# ESP32_USBC.net
KiCad netlist of a schematic drawn in Altium Designer
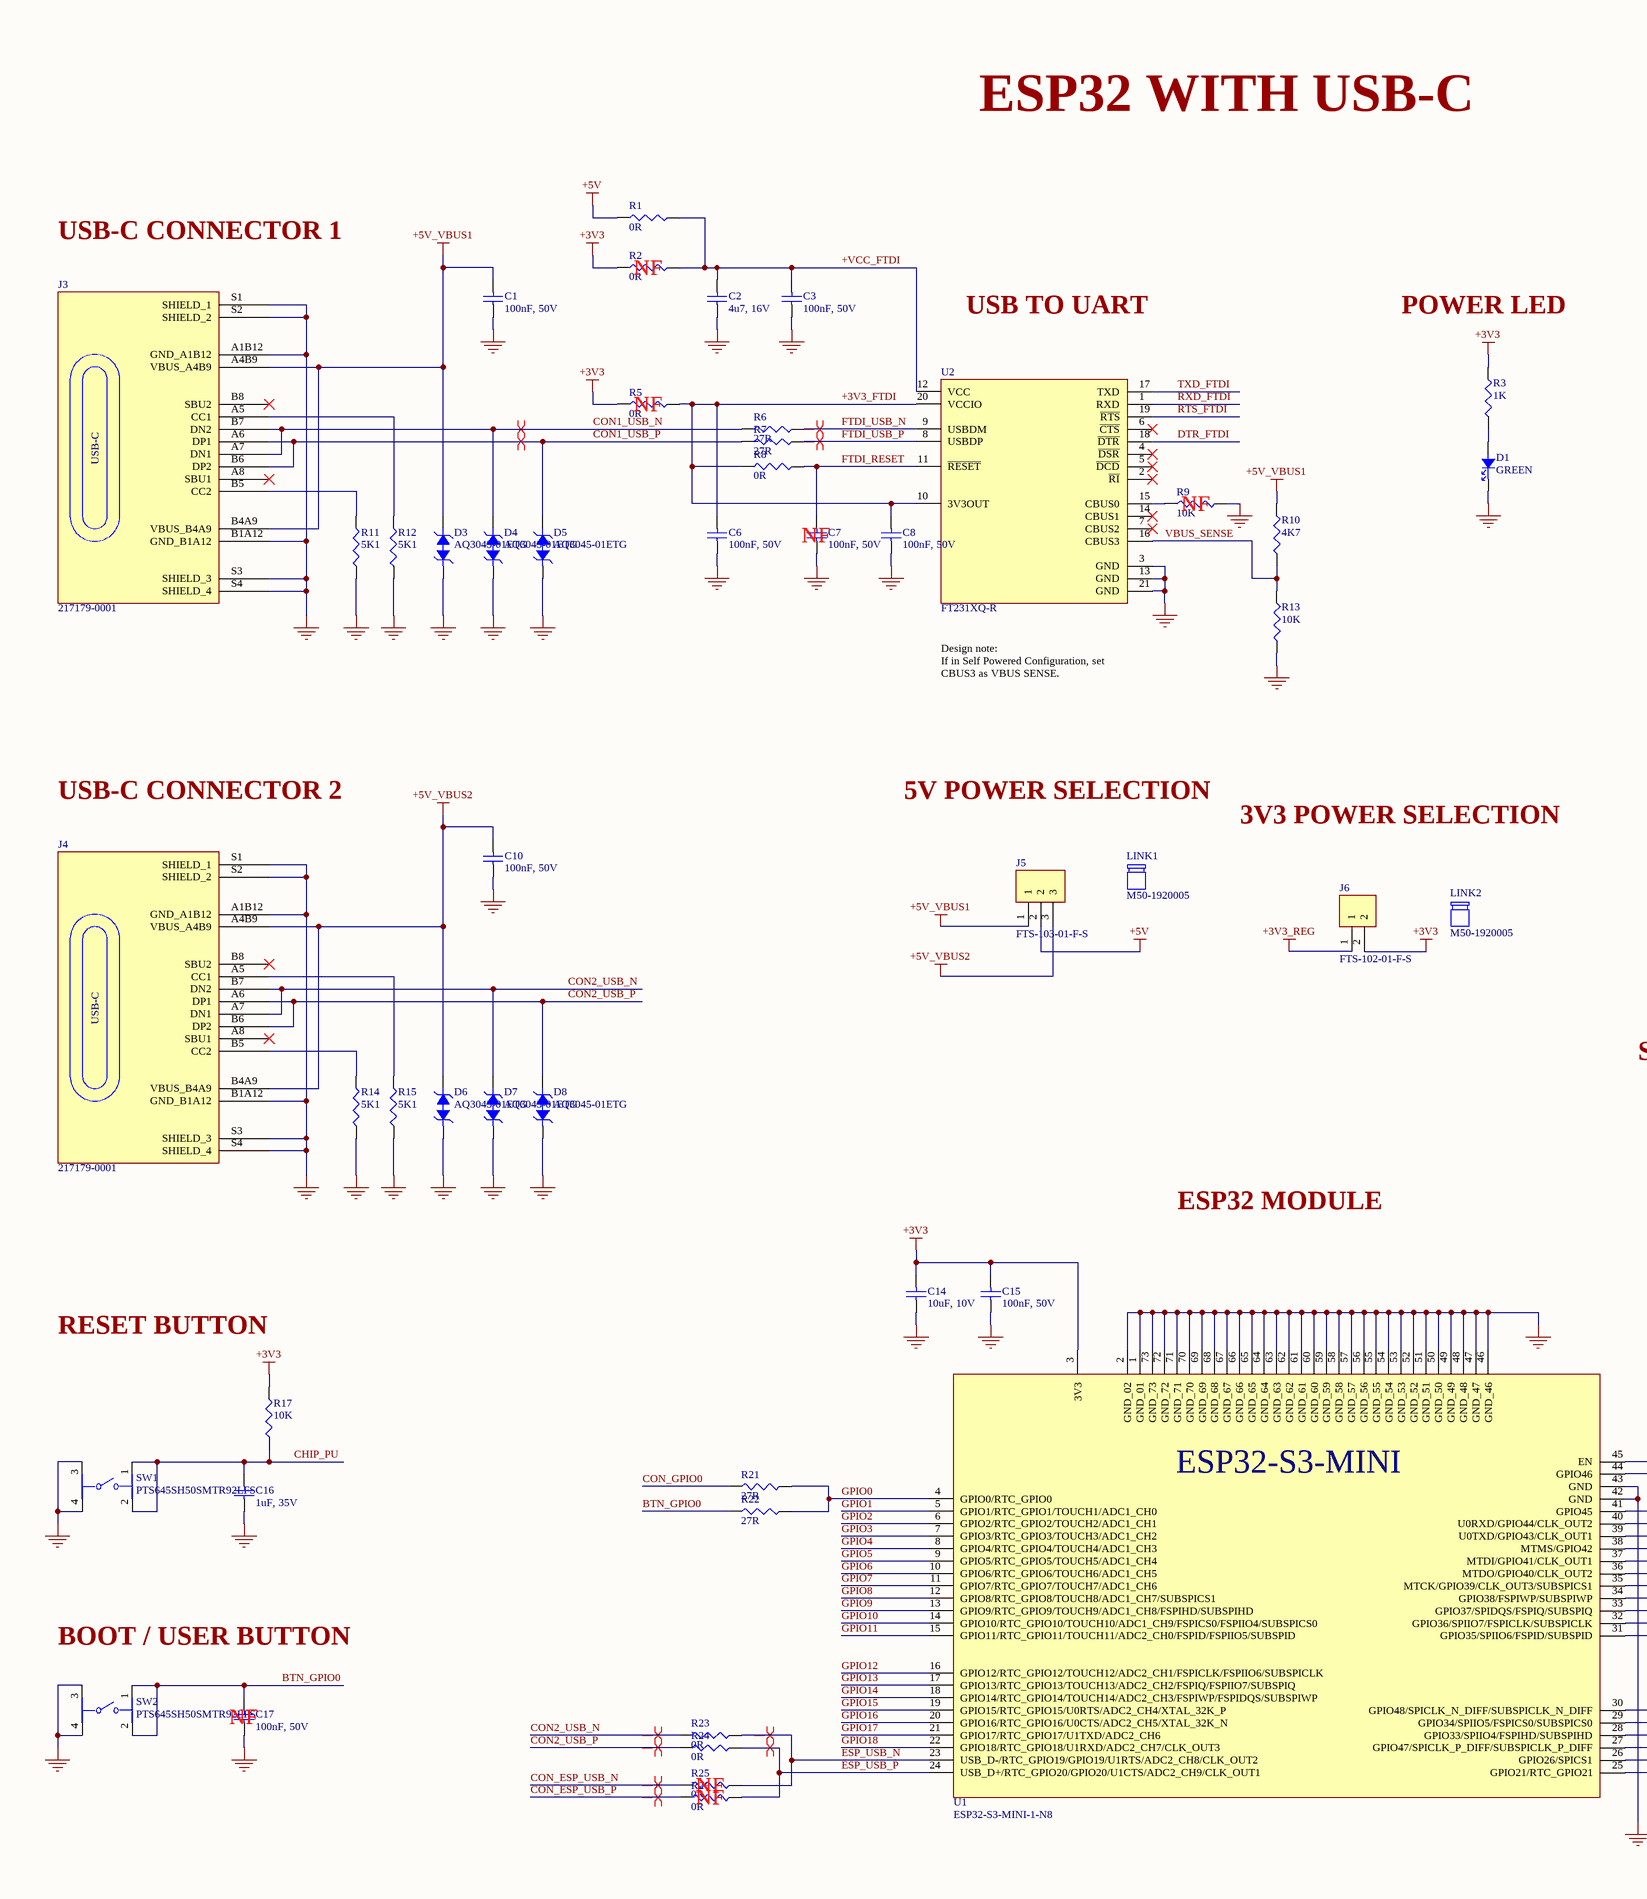
[diagram p0: ESP32_USBC.SchDoc, left]
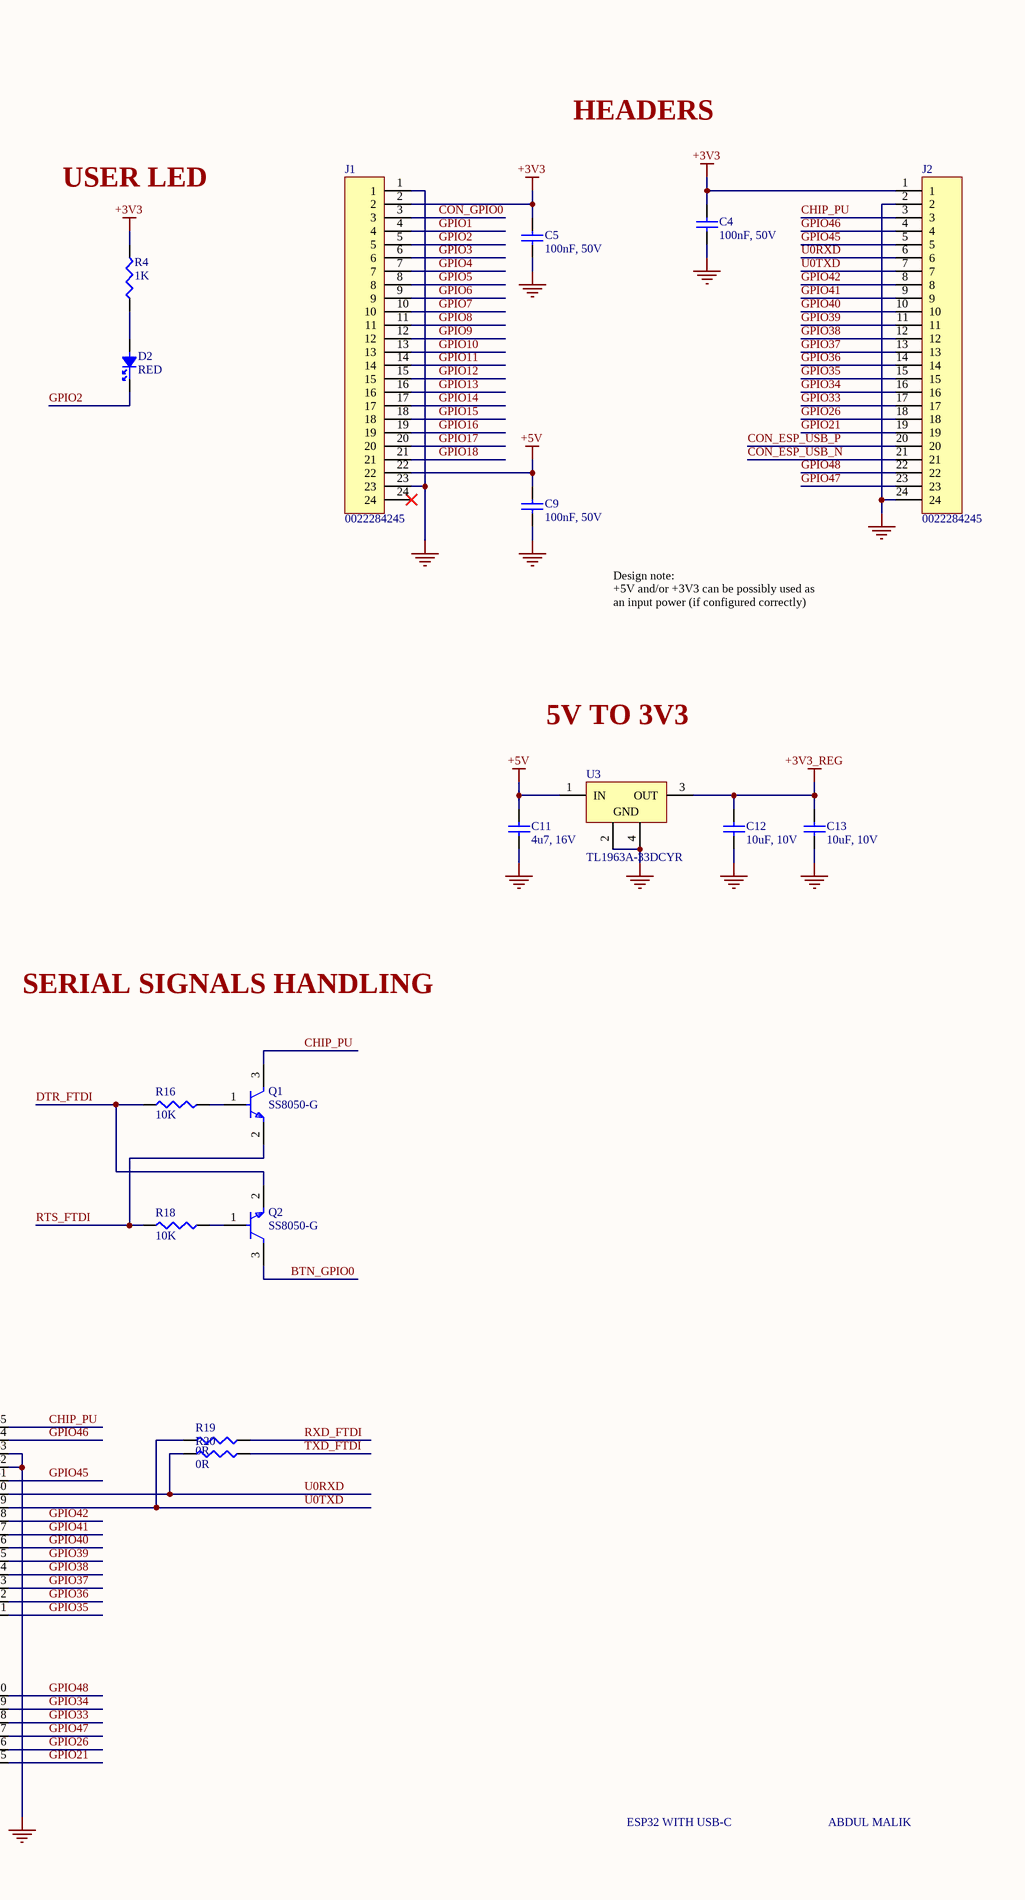
[diagram p1: ESP32_USBC.SchDoc, right]

(export (version "E")
  (design (tool "Eeschema 10.0.6"))
  (components
    (comp (ref "C1")
      (value "100nF, 50V")
      (footprint "CAPC1005X55N")
      (description "CAP CER 0.1UF 50V X7R 0402")
      (fields
        (field (name "MANUFACTURER") "Samsung")
        (field (name "MANUFACTURER PART NUMBER") "CL05B104KB54PNC")
      )
      (libsource (lib "Schlib") (part "CL05B104KB54PNC"))
    )
    (comp (ref "C2")
      (value "4u7, 16V")
      (footprint "CAPC1005X55N")
      (description "CAP CER 4.7UF 16V X5R 0402")
      (fields
        (field (name "MANUFACTURER") "Samsung")
        (field (name "MANUFACTURER PART NUMBER") "CL05A475MO5NUNC")
      )
      (libsource (lib "Schlib") (part "CL05A475MO5NUNC"))
    )
    (comp (ref "C3")
      (value "100nF, 50V")
      (footprint "CAPC1005X55N")
      (description "CAP CER 0.1UF 50V X7R 0402")
      (fields
        (field (name "MANUFACTURER") "Samsung")
        (field (name "MANUFACTURER PART NUMBER") "CL05B104KB54PNC")
      )
      (libsource (lib "Schlib") (part "CL05B104KB54PNC"))
    )
    (comp (ref "C4")
      (value "100nF, 50V")
      (footprint "CAPC1005X55N")
      (description "CAP CER 0.1UF 50V X7R 0402")
      (fields
        (field (name "MANUFACTURER") "Samsung")
        (field (name "MANUFACTURER PART NUMBER") "CL05B104KB54PNC")
      )
      (libsource (lib "Schlib") (part "CL05B104KB54PNC"))
    )
    (comp (ref "C5")
      (value "100nF, 50V")
      (footprint "CAPC1005X55N")
      (description "CAP CER 0.1UF 50V X7R 0402")
      (fields
        (field (name "MANUFACTURER") "Samsung")
        (field (name "MANUFACTURER PART NUMBER") "CL05B104KB54PNC")
      )
      (libsource (lib "Schlib") (part "CL05B104KB54PNC"))
    )
    (comp (ref "C6")
      (value "100nF, 50V")
      (footprint "CAPC1005X55N")
      (description "CAP CER 0.1UF 50V X7R 0402")
      (fields
        (field (name "MANUFACTURER") "Samsung")
        (field (name "MANUFACTURER PART NUMBER") "CL05B104KB54PNC")
      )
      (libsource (lib "Schlib") (part "CL05B104KB54PNC"))
    )
    (comp (ref "C7")
      (value "100nF, 50V")
      (footprint "CAPC1005X55N")
      (description "CAP CER 0.1UF 50V X7R 0402")
      (fields
        (field (name "MANUFACTURER") "Samsung")
        (field (name "MANUFACTURER PART NUMBER") "CL05B104KB54PNC")
      )
      (libsource (lib "Schlib") (part "CL05B104KB54PNC"))
    )
    (comp (ref "C8")
      (value "100nF, 50V")
      (footprint "CAPC1005X55N")
      (description "CAP CER 0.1UF 50V X7R 0402")
      (fields
        (field (name "MANUFACTURER") "Samsung")
        (field (name "MANUFACTURER PART NUMBER") "CL05B104KB54PNC")
      )
      (libsource (lib "Schlib") (part "CL05B104KB54PNC"))
    )
    (comp (ref "C9")
      (value "100nF, 50V")
      (footprint "CAPC1005X55N")
      (description "CAP CER 0.1UF 50V X7R 0402")
      (fields
        (field (name "MANUFACTURER") "Samsung")
        (field (name "MANUFACTURER PART NUMBER") "CL05B104KB54PNC")
      )
      (libsource (lib "Schlib") (part "CL05B104KB54PNC"))
    )
    (comp (ref "C10")
      (value "100nF, 50V")
      (footprint "CAPC1005X55N")
      (description "CAP CER 0.1UF 50V X7R 0402")
      (fields
        (field (name "MANUFACTURER") "Samsung")
        (field (name "MANUFACTURER PART NUMBER") "CL05B104KB54PNC")
      )
      (libsource (lib "Schlib") (part "CL05B104KB54PNC"))
    )
    (comp (ref "C11")
      (value "4u7, 16V")
      (footprint "CAPC1005X55N")
      (description "CAP CER 4.7UF 16V X5R 0402")
      (fields
        (field (name "MANUFACTURER") "Samsung")
        (field (name "MANUFACTURER PART NUMBER") "CL05A475MO5NUNC")
      )
      (libsource (lib "Schlib") (part "CL05A475MO5NUNC"))
    )
    (comp (ref "C12")
      (value "10uF, 10V")
      (footprint "CAPC1005X55N")
      (description "CAP CER 10UF 10V X5R 0402")
      (fields
        (field (name "MANUFACTURER") "Samsung")
        (field (name "MANUFACTURER PART NUMBER") "CL05A106MP8NUB8")
      )
      (libsource (lib "Schlib") (part "CL05A106MP8NUB8"))
    )
    (comp (ref "C13")
      (value "10uF, 10V")
      (footprint "CAPC1005X55N")
      (description "CAP CER 10UF 10V X5R 0402")
      (fields
        (field (name "MANUFACTURER") "Samsung")
        (field (name "MANUFACTURER PART NUMBER") "CL05A106MP8NUB8")
      )
      (libsource (lib "Schlib") (part "CL05A106MP8NUB8"))
    )
    (comp (ref "C14")
      (value "10uF, 10V")
      (footprint "CAPC1005X55N")
      (description "CAP CER 10UF 10V X5R 0402")
      (fields
        (field (name "MANUFACTURER") "Samsung")
        (field (name "MANUFACTURER PART NUMBER") "CL05A106MP8NUB8")
      )
      (libsource (lib "Schlib") (part "CL05A106MP8NUB8"))
    )
    (comp (ref "C15")
      (value "100nF, 50V")
      (footprint "CAPC1005X55N")
      (description "CAP CER 0.1UF 50V X7R 0402")
      (fields
        (field (name "MANUFACTURER") "Samsung")
        (field (name "MANUFACTURER PART NUMBER") "CL05B104KB54PNC")
      )
      (libsource (lib "Schlib") (part "CL05B104KB54PNC"))
    )
    (comp (ref "C16")
      (value "1uF, 35V")
      (footprint "CAPC1005X55N")
      (description "CAP CER 1UF 35V X5R 0402")
      (fields
        (field (name "MANUFACTURER") "Samsung")
        (field (name "MANUFACTURER PART NUMBER") "CL05A105KL5NRNC")
      )
      (libsource (lib "Schlib") (part "CL05A105KL5NRNC"))
    )
    (comp (ref "C17")
      (value "100nF, 50V")
      (footprint "CAPC1005X55N")
      (description "CAP CER 0.1UF 50V X7R 0402")
      (fields
        (field (name "MANUFACTURER") "Samsung")
        (field (name "MANUFACTURER PART NUMBER") "CL05B104KB54PNC")
      )
      (libsource (lib "Schlib") (part "CL05B104KB54PNC"))
    )
    (comp (ref "D1")
      (value "GREEN")
      (footprint "LED0402G")
      (description "LED YLW-GRN 0402 SMD")
      (fields
        (field (name "MANUFACTURER") "Vishay")
        (field (name "MANUFACTURER PART NUMBER") "VLMG1500-GS08")
      )
      (libsource (lib "Schlib") (part "VLMG1500-GS08"))
    )
    (comp (ref "D2")
      (value "RED")
      (footprint "LED0402R")
      (description "LED RED 0402 SMD")
      (fields
        (field (name "MANUFACTURER") "Vishay")
        (field (name "MANUFACTURER PART NUMBER") "VLMS1500-GS08")
      )
      (libsource (lib "Schlib") (part "VLMS1500-GS08"))
    )
    (comp (ref "D3")
      (value "AQ3045-01ETG")
      (footprint "SOD882")
      (description "TVS DIODE 5.3VWM 12VC SOD882")
      (fields (field (name "MANUFACTURER") "Littelfuse") (field (name "LCSC PART NUMBER") "C3710326"))
      (libsource (lib "Schlib") (part "AQ3045-01ETG"))
    )
    (comp (ref "D4")
      (value "AQ3045-01ETG")
      (footprint "SOD882")
      (description "TVS DIODE 5.3VWM 12VC SOD882")
      (fields (field (name "MANUFACTURER") "Littelfuse") (field (name "LCSC PART NUMBER") "C3710326"))
      (libsource (lib "Schlib") (part "AQ3045-01ETG"))
    )
    (comp (ref "D5")
      (value "AQ3045-01ETG")
      (footprint "SOD882")
      (description "TVS DIODE 5.3VWM 12VC SOD882")
      (fields (field (name "MANUFACTURER") "Littelfuse") (field (name "LCSC PART NUMBER") "C3710326"))
      (libsource (lib "Schlib") (part "AQ3045-01ETG"))
    )
    (comp (ref "D6")
      (value "AQ3045-01ETG")
      (footprint "SOD882")
      (description "TVS DIODE 5.3VWM 12VC SOD882")
      (fields (field (name "MANUFACTURER") "Littelfuse") (field (name "LCSC PART NUMBER") "C3710326"))
      (libsource (lib "Schlib") (part "AQ3045-01ETG"))
    )
    (comp (ref "D7")
      (value "AQ3045-01ETG")
      (footprint "SOD882")
      (description "TVS DIODE 5.3VWM 12VC SOD882")
      (fields (field (name "MANUFACTURER") "Littelfuse") (field (name "LCSC PART NUMBER") "C3710326"))
      (libsource (lib "Schlib") (part "AQ3045-01ETG"))
    )
    (comp (ref "D8")
      (value "AQ3045-01ETG")
      (footprint "SOD882")
      (description "TVS DIODE 5.3VWM 12VC SOD882")
      (fields (field (name "MANUFACTURER") "Littelfuse") (field (name "LCSC PART NUMBER") "C3710326"))
      (libsource (lib "Schlib") (part "AQ3045-01ETG"))
    )
    (comp (ref "J1")
      (value "0022284245")
      (footprint "HDR_1X24_2.54MM")
      (description "CONN HEADER VERT 24POS 2.54MM")
      (fields (field (name "MANUFACTURER") "Molex") (field (name "LCSC PART NUMBER") "C7145888"))
      (libsource (lib "") (part "0022284245_1"))
    )
    (comp (ref "J2")
      (value "0022284245")
      (footprint "HDR_1X24_2.54MM")
      (description "CONN HEADER VERT 24POS 2.54MM")
      (fields (field (name "MANUFACTURER") "Molex") (field (name "LCSC PART NUMBER") "C7145888"))
      (libsource (lib "Schlib") (part "0022284245"))
    )
    (comp (ref "J3")
      (value "217179-0001")
      (footprint "FP-2171790001-MFG")
      (description "CONN RCP USB2.0 TYP C 24P SMD RA")
      (fields (field (name "MANUFACTURER") "Molex") (field (name "LCSC PART NUMBER") "C3197684"))
      (libsource (lib "Schlib") (part "217179-0001"))
    )
    (comp (ref "J4")
      (value "217179-0001")
      (footprint "FP-2171790001-MFG")
      (description "CONN RCP USB2.0 TYP C 24P SMD RA")
      (fields (field (name "MANUFACTURER") "Molex") (field (name "LCSC PART NUMBER") "C3197684"))
      (libsource (lib "Schlib") (part "217179-0001"))
    )
    (comp (ref "J5")
      (value "FTS-103-01-F-S")
      (footprint "HDR_1X3_1.27MM")
      (description "CONN HEADER VERT 3POS 1.27MM")
      (fields (field (name "MANUFACTURER") "Samtec") (field (name "LCSC PART NUMBER") "C3333578"))
      (libsource (lib "Schlib") (part "FTS-103-01-F-S"))
    )
    (comp (ref "J6")
      (value "FTS-102-01-F-S")
      (footprint "HDR_1X2_1.27MM")
      (description "CONN HEADER VERT 2POS 1.27MM")
      (fields (field (name "MANUFACTURER") "Samtec") (field (name "LCSC PART NUMBER") "C6045317"))
      (libsource (lib "Schlib") (part "FTS-102-01-F-S"))
    )
    (comp (ref "LINK1")
      (value "M50-1920005")
      (description "CONN SHUNT 1.27MM RED")
      (fields (field (name "MANUFACTURER") "Harwin") (field (name "LCSC PART NUMBER") "C6985646"))
      (libsource (lib "Schlib") (part "M50-1920005"))
    )
    (comp (ref "LINK2")
      (value "M50-1920005")
      (description "CONN SHUNT 1.27MM RED")
      (fields (field (name "MANUFACTURER") "Harwin") (field (name "LCSC PART NUMBER") "C6985646"))
      (libsource (lib "Schlib") (part "M50-1920005"))
    )
    (comp (ref "Q1")
      (value "SS8050-G")
      (footprint "FP-SS8050-G-IPC_B")
      (description "TRANS NPN 25V 1.5A SOT23-3")
      (fields (field (name "MANUFACTURER") "Comchip") (field (name "LCSC PART NUMBER") "C164886"))
      (libsource (lib "Schlib") (part "SS8050-G"))
    )
    (comp (ref "Q2")
      (value "SS8050-G")
      (footprint "FP-SS8050-G-IPC_B")
      (description "TRANS NPN 25V 1.5A SOT23-3")
      (fields (field (name "MANUFACTURER") "Comchip") (field (name "LCSC PART NUMBER") "C164886"))
      (libsource (lib "Schlib") (part "SS8050-G"))
    )
    (comp (ref "R1")
      (value "0R")
      (footprint "RESC1005X37N")
      (description "RES 0 OHM JUMPER 1/16W 0402")
      (fields
        (field (name "MANUFACTURER") "Yageo")
        (field (name "MANUFACTURER PART NUMBER") "RC0402JR-070RL")
      )
      (libsource (lib "Schlib") (part "RC0402JR-070RL"))
    )
    (comp (ref "R2")
      (value "0R")
      (footprint "RESC1005X37N")
      (description "RES 0 OHM JUMPER 1/16W 0402")
      (fields
        (field (name "MANUFACTURER") "Yageo")
        (field (name "MANUFACTURER PART NUMBER") "RC0402JR-070RL")
      )
      (libsource (lib "Schlib") (part "RC0402JR-070RL"))
    )
    (comp (ref "R3")
      (value "1K")
      (footprint "RESC1005X37N")
      (description "RES 1K OHM 1% 1/16W 0402")
      (fields
        (field (name "MANUFACTURER") "Yageo")
        (field (name "MANUFACTURER PART NUMBER") "RC0402FR-071KL")
      )
      (libsource (lib "Schlib") (part "RC0402FR-071KL"))
    )
    (comp (ref "R4")
      (value "1K")
      (footprint "RESC1005X37N")
      (description "RES 1K OHM 1% 1/16W 0402")
      (fields
        (field (name "MANUFACTURER") "Yageo")
        (field (name "MANUFACTURER PART NUMBER") "RC0402FR-071KL")
      )
      (libsource (lib "Schlib") (part "RC0402FR-071KL"))
    )
    (comp (ref "R5")
      (value "0R")
      (footprint "RESC1005X37N")
      (description "RES 0 OHM JUMPER 1/16W 0402")
      (fields
        (field (name "MANUFACTURER") "Yageo")
        (field (name "MANUFACTURER PART NUMBER") "RC0402JR-070RL")
      )
      (libsource (lib "Schlib") (part "RC0402JR-070RL"))
    )
    (comp (ref "R6")
      (value "27R")
      (footprint "RESC1005X37N")
      (description "RES 27 OHM 1% 1/16W 0402")
      (fields
        (field (name "MANUFACTURER") "Yageo")
        (field (name "MANUFACTURER PART NUMBER") "RC0402FR-0727RL")
      )
      (libsource (lib "Schlib") (part "RC0402FR-0727RL"))
    )
    (comp (ref "R7")
      (value "27R")
      (footprint "RESC1005X37N")
      (description "RES 27 OHM 1% 1/16W 0402")
      (fields
        (field (name "MANUFACTURER") "Yageo")
        (field (name "MANUFACTURER PART NUMBER") "RC0402FR-0727RL")
      )
      (libsource (lib "Schlib") (part "RC0402FR-0727RL"))
    )
    (comp (ref "R8")
      (value "0R")
      (footprint "RESC1005X37N")
      (description "RES 0 OHM JUMPER 1/16W 0402")
      (fields
        (field (name "MANUFACTURER") "Yageo")
        (field (name "MANUFACTURER PART NUMBER") "RC0402JR-070RL")
      )
      (libsource (lib "Schlib") (part "RC0402JR-070RL"))
    )
    (comp (ref "R9")
      (value "10K")
      (footprint "RESC1005X37N")
      (description "RES SMD 10K OHM 1% 1/16W 0402")
      (fields
        (field (name "MANUFACTURER") "Yageo")
        (field (name "MANUFACTURER PART NUMBER") "AC0402FR-0710KL")
      )
      (libsource (lib "Schlib") (part "AC0402FR-0710KL"))
    )
    (comp (ref "R10")
      (value "4K7")
      (footprint "RESC1005X37N")
      (description "RES 4.7K OHM 1% 1/16W 0402")
      (fields
        (field (name "MANUFACTURER") "Yageo")
        (field (name "MANUFACTURER PART NUMBER") "RC0402FR-074K7L")
      )
      (libsource (lib "Schlib") (part "RC0402FR-074K7L"))
    )
    (comp (ref "R11")
      (value "5K1")
      (footprint "RESC1005X37N")
      (description "RES SMD 5.1K OHM 1% 1/16W 0402")
      (fields
        (field (name "MANUFACTURER") "Yageo")
        (field (name "MANUFACTURER PART NUMBER") "AC0402FR-075K1L")
      )
      (libsource (lib "Schlib") (part "AC0402FR-075K1L"))
    )
    (comp (ref "R12")
      (value "5K1")
      (footprint "RESC1005X37N")
      (description "RES SMD 5.1K OHM 1% 1/16W 0402")
      (fields
        (field (name "MANUFACTURER") "Yageo")
        (field (name "MANUFACTURER PART NUMBER") "AC0402FR-075K1L")
      )
      (libsource (lib "Schlib") (part "AC0402FR-075K1L"))
    )
    (comp (ref "R13")
      (value "10K")
      (footprint "RESC1005X37N")
      (description "RES SMD 10K OHM 1% 1/16W 0402")
      (fields
        (field (name "MANUFACTURER") "Yageo")
        (field (name "MANUFACTURER PART NUMBER") "AC0402FR-0710KL")
      )
      (libsource (lib "Schlib") (part "AC0402FR-0710KL"))
    )
    (comp (ref "R14")
      (value "5K1")
      (footprint "RESC1005X37N")
      (description "RES SMD 5.1K OHM 1% 1/16W 0402")
      (fields
        (field (name "MANUFACTURER") "Yageo")
        (field (name "MANUFACTURER PART NUMBER") "AC0402FR-075K1L")
      )
      (libsource (lib "Schlib") (part "AC0402FR-075K1L"))
    )
    (comp (ref "R15")
      (value "5K1")
      (footprint "RESC1005X37N")
      (description "RES SMD 5.1K OHM 1% 1/16W 0402")
      (fields
        (field (name "MANUFACTURER") "Yageo")
        (field (name "MANUFACTURER PART NUMBER") "AC0402FR-075K1L")
      )
      (libsource (lib "Schlib") (part "AC0402FR-075K1L"))
    )
    (comp (ref "R16")
      (value "10K")
      (footprint "RESC1005X37N")
      (description "RES SMD 10K OHM 1% 1/16W 0402")
      (fields
        (field (name "MANUFACTURER") "Yageo")
        (field (name "MANUFACTURER PART NUMBER") "AC0402FR-0710KL")
      )
      (libsource (lib "Schlib") (part "AC0402FR-0710KL"))
    )
    (comp (ref "R17")
      (value "10K")
      (footprint "RESC1005X37N")
      (description "RES SMD 10K OHM 1% 1/16W 0402")
      (fields
        (field (name "MANUFACTURER") "Yageo")
        (field (name "MANUFACTURER PART NUMBER") "AC0402FR-0710KL")
      )
      (libsource (lib "Schlib") (part "AC0402FR-0710KL"))
    )
    (comp (ref "R18")
      (value "10K")
      (footprint "RESC1005X37N")
      (description "RES SMD 10K OHM 1% 1/16W 0402")
      (fields
        (field (name "MANUFACTURER") "Yageo")
        (field (name "MANUFACTURER PART NUMBER") "AC0402FR-0710KL")
      )
      (libsource (lib "Schlib") (part "AC0402FR-0710KL"))
    )
    (comp (ref "R19")
      (value "0R")
      (footprint "RESC1005X37N")
      (description "RES 0 OHM JUMPER 1/16W 0402")
      (fields
        (field (name "MANUFACTURER") "Yageo")
        (field (name "MANUFACTURER PART NUMBER") "RC0402JR-070RL")
      )
      (libsource (lib "Schlib") (part "RC0402JR-070RL"))
    )
    (comp (ref "R20")
      (value "0R")
      (footprint "RESC1005X37N")
      (description "RES 0 OHM JUMPER 1/16W 0402")
      (fields
        (field (name "MANUFACTURER") "Yageo")
        (field (name "MANUFACTURER PART NUMBER") "RC0402JR-070RL")
      )
      (libsource (lib "Schlib") (part "RC0402JR-070RL"))
    )
    (comp (ref "R21")
      (value "27R")
      (footprint "RESC1005X37N")
      (description "RES 27 OHM 1% 1/16W 0402")
      (fields
        (field (name "MANUFACTURER") "Yageo")
        (field (name "MANUFACTURER PART NUMBER") "RC0402FR-0727RL")
      )
      (libsource (lib "Schlib") (part "RC0402FR-0727RL"))
    )
    (comp (ref "R22")
      (value "27R")
      (footprint "RESC1005X37N")
      (description "RES 27 OHM 1% 1/16W 0402")
      (fields
        (field (name "MANUFACTURER") "Yageo")
        (field (name "MANUFACTURER PART NUMBER") "RC0402FR-0727RL")
      )
      (libsource (lib "Schlib") (part "RC0402FR-0727RL"))
    )
    (comp (ref "R23")
      (value "0R")
      (footprint "RESC1005X37N")
      (description "RES 0 OHM JUMPER 1/16W 0402")
      (fields
        (field (name "MANUFACTURER") "Yageo")
        (field (name "MANUFACTURER PART NUMBER") "RC0402JR-070RL")
      )
      (libsource (lib "Schlib") (part "RC0402JR-070RL"))
    )
    (comp (ref "R24")
      (value "0R")
      (footprint "RESC1005X37N")
      (description "RES 0 OHM JUMPER 1/16W 0402")
      (fields
        (field (name "MANUFACTURER") "Yageo")
        (field (name "MANUFACTURER PART NUMBER") "RC0402JR-070RL")
      )
      (libsource (lib "Schlib") (part "RC0402JR-070RL"))
    )
    (comp (ref "R25")
      (value "0R")
      (footprint "RESC1005X37N")
      (description "RES 0 OHM JUMPER 1/16W 0402")
      (fields
        (field (name "MANUFACTURER") "Yageo")
        (field (name "MANUFACTURER PART NUMBER") "RC0402JR-070RL")
      )
      (libsource (lib "Schlib") (part "RC0402JR-070RL"))
    )
    (comp (ref "R26")
      (value "0R")
      (footprint "RESC1005X37N")
      (description "RES 0 OHM JUMPER 1/16W 0402")
      (fields
        (field (name "MANUFACTURER") "Yageo")
        (field (name "MANUFACTURER PART NUMBER") "RC0402JR-070RL")
      )
      (libsource (lib "Schlib") (part "RC0402JR-070RL"))
    )
    (comp (ref "SW1")
      (value "PTS645SH50SMTR92LFS")
      (footprint "FP-PTS645SH50SMTR92LFS-MFG")
      (description "SWITCH TACTILE SPST-NO 0.05A 12V")
      (fields (field (name "MANUFACTURER") "ITT C&K") (field (name "LCSC PART NUMBER") "C221869"))
      (libsource (lib "Schlib") (part "PTS645SH50SMTR92LFS"))
    )
    (comp (ref "SW2")
      (value "PTS645SH50SMTR92LFS")
      (footprint "FP-PTS645SH50SMTR92LFS-MFG")
      (description "SWITCH TACTILE SPST-NO 0.05A 12V")
      (fields (field (name "MANUFACTURER") "ITT C&K") (field (name "LCSC PART NUMBER") "C221869"))
      (libsource (lib "Schlib") (part "PTS645SH50SMTR92LFS"))
    )
    (comp (ref "U1")
      (value "ESP32-S3-MINI-1-N8")
      (footprint "XCVR_ESP32-S3-MINI-1-N8")
      (description "SMD Module, ESP32-S3FN8, 8 mb Sp")
      (fields (field (name "MANUFACTURER") "Espressif Systems") (field (name "LCSC PART NUMBER") "C2913206"))
      (libsource (lib "Schlib") (part "ESP32-S3-MINI-1-N8"))
    )
    (comp (ref "U2")
      (value "FT231XQ-R")
      (footprint "FP-QFN-20-IPC_B")
      (description "IC USB SERIAL FULL UART 20QFN")
      (fields (field (name "MANUFACTURER") "FTDI") (field (name "LCSC PART NUMBER") "C132159"))
      (libsource (lib "Schlib") (part "FT231XQ-R"))
    )
    (comp (ref "U3")
      (value "TL1963A-33DCYR")
      (footprint "DCY0004A_N")
      (description "IC REG LINEAR 3.3V 1.5A SOT223-4")
      (fields (field (name "MANUFACTURER") "Texas Instruments") (field (name "LCSC PART NUMBER") "C181262"))
      (libsource (lib "Schlib") (part "TL1963A-33DCYR"))
    )
  )
  (nets
    (net (code "1") (name "+3V3") (class "Default")
      (node (ref "C14") (pin "2") (pinfunction "2_2") (pintype "passive"))
      (node (ref "C15") (pin "2") (pinfunction "2_2") (pintype "passive"))
      (node (ref "C4") (pin "2") (pinfunction "2_2") (pintype "passive"))
      (node (ref "C5") (pin "2") (pinfunction "2_2") (pintype "passive"))
      (node (ref "J1") (pin "2") (pinfunction "2_2") (pintype "passive"))
      (node (ref "J2") (pin "1") (pinfunction "1_1") (pintype "passive"))
      (node (ref "J6") (pin "2") (pinfunction "2_2") (pintype "passive"))
      (node (ref "R17") (pin "2") (pinfunction "2_2") (pintype "passive"))
      (node (ref "R2") (pin "1") (pinfunction "1_1") (pintype "passive"))
      (node (ref "R3") (pin "2") (pinfunction "2_2") (pintype "passive"))
      (node (ref "R4") (pin "2") (pinfunction "2_2") (pintype "passive"))
      (node (ref "R5") (pin "1") (pinfunction "1_1") (pintype "passive"))
      (node (ref "U1") (pin "3") (pinfunction "3V3_3") (pintype "passive"))
    )
    (net (code "2") (name "+3V3_REG") (class "Default")
      (node (ref "C12") (pin "2") (pinfunction "2_2") (pintype "passive"))
      (node (ref "C13") (pin "2") (pinfunction "2_2") (pintype "passive"))
      (node (ref "J6") (pin "1") (pinfunction "1_1") (pintype "passive"))
      (node (ref "U3") (pin "3") (pinfunction "OUT_3") (pintype "power_in"))
    )
    (net (code "3") (name "+5V") (class "Default")
      (node (ref "C11") (pin "2") (pinfunction "2_2") (pintype "passive"))
      (node (ref "C9") (pin "2") (pinfunction "2_2") (pintype "passive"))
      (node (ref "J1") (pin "22") (pinfunction "22_22") (pintype "passive"))
      (node (ref "J5") (pin "2") (pinfunction "2_2") (pintype "passive"))
      (node (ref "R1") (pin "1") (pinfunction "1_1") (pintype "passive"))
      (node (ref "U3") (pin "1") (pinfunction "IN_1") (pintype "power_in"))
    )
    (net (code "4") (name "+5V_VBUS1") (class "Default")
      (node (ref "C1") (pin "2") (pinfunction "2_2") (pintype "passive"))
      (node (ref "D3") (pin "2") (pinfunction "2_2") (pintype "passive"))
      (node (ref "J3") (pin "A4B9") (pinfunction "VBUS_A4B9_A4B9") (pintype "passive"))
      (node (ref "J3") (pin "B4A9") (pinfunction "VBUS_B4A9_B4A9") (pintype "passive"))
      (node (ref "J5") (pin "1") (pinfunction "1_1") (pintype "passive"))
      (node (ref "R10") (pin "2") (pinfunction "2_2") (pintype "passive"))
    )
    (net (code "5") (name "+5V_VBUS2") (class "Default")
      (node (ref "C10") (pin "2") (pinfunction "2_2") (pintype "passive"))
      (node (ref "D6") (pin "2") (pinfunction "2_2") (pintype "passive"))
      (node (ref "J4") (pin "A4B9") (pinfunction "VBUS_A4B9_A4B9") (pintype "passive"))
      (node (ref "J4") (pin "B4A9") (pinfunction "VBUS_B4A9_B4A9") (pintype "passive"))
      (node (ref "J5") (pin "3") (pinfunction "3_3") (pintype "passive"))
    )
    (net (code "6") (name "/+3V3_FTDI") (class "Default")
      (node (ref "C6") (pin "2") (pinfunction "2_2") (pintype "passive"))
      (node (ref "C8") (pin "2") (pinfunction "2_2") (pintype "passive"))
      (node (ref "R5") (pin "2") (pinfunction "2_2") (pintype "passive"))
      (node (ref "R8") (pin "1") (pinfunction "1_1") (pintype "passive"))
      (node (ref "U2") (pin "10") (pinfunction "3V3OUT_10") (pintype "passive"))
      (node (ref "U2") (pin "20") (pinfunction "VCCIO_20") (pintype "passive"))
    )
    (net (code "7") (name "/+VCC_FTDI") (class "Default")
      (node (ref "C2") (pin "2") (pinfunction "2_2") (pintype "passive"))
      (node (ref "C3") (pin "2") (pinfunction "2_2") (pintype "passive"))
      (node (ref "R1") (pin "2") (pinfunction "2_2") (pintype "passive"))
      (node (ref "R2") (pin "2") (pinfunction "2_2") (pintype "passive"))
      (node (ref "U2") (pin "12") (pinfunction "VCC_12") (pintype "passive"))
    )
    (net (code "8") (name "/BTN_GPIO0") (class "Default")
      (node (ref "C17") (pin "2") (pinfunction "2_2") (pintype "passive"))
      (node (ref "Q2") (pin "3") (pinfunction "C_3") (pintype "passive"))
      (node (ref "R22") (pin "1") (pinfunction "1_1") (pintype "passive"))
      (node (ref "SW2") (pin "1") (pinfunction "1_1") (pintype "passive"))
      (node (ref "SW2") (pin "2") (pinfunction "2_2") (pintype "passive"))
    )
    (net (code "9") (name "/CHIP_PU") (class "Default")
      (node (ref "C16") (pin "2") (pinfunction "2_2") (pintype "passive"))
      (node (ref "J2") (pin "3") (pinfunction "3_3") (pintype "passive"))
      (node (ref "Q1") (pin "3") (pinfunction "C_3") (pintype "passive"))
      (node (ref "R17") (pin "1") (pinfunction "1_1") (pintype "passive"))
      (node (ref "SW1") (pin "1") (pinfunction "1_1") (pintype "passive"))
      (node (ref "SW1") (pin "2") (pinfunction "2_2") (pintype "passive"))
      (node (ref "U1") (pin "45") (pinfunction "EN_45") (pintype "passive"))
    )
    (net (code "10") (name "/CON1_USB_N") (class "Default")
      (node (ref "D4") (pin "2") (pinfunction "2_2") (pintype "passive"))
      (node (ref "J3") (pin "A7") (pinfunction "DN1_A7") (pintype "passive"))
      (node (ref "J3") (pin "B7") (pinfunction "DN2_B7") (pintype "passive"))
      (node (ref "R6") (pin "1") (pinfunction "1_1") (pintype "passive"))
    )
    (net (code "11") (name "/CON1_USB_P") (class "Default")
      (node (ref "D5") (pin "2") (pinfunction "2_2") (pintype "passive"))
      (node (ref "J3") (pin "A6") (pinfunction "DP1_A6") (pintype "passive"))
      (node (ref "J3") (pin "B6") (pinfunction "DP2_B6") (pintype "passive"))
      (node (ref "R7") (pin "1") (pinfunction "1_1") (pintype "passive"))
    )
    (net (code "12") (name "/CON2_USB_N") (class "Default")
      (node (ref "D7") (pin "2") (pinfunction "2_2") (pintype "passive"))
      (node (ref "J4") (pin "A7") (pinfunction "DN1_A7") (pintype "passive"))
      (node (ref "J4") (pin "B7") (pinfunction "DN2_B7") (pintype "passive"))
      (node (ref "R23") (pin "1") (pinfunction "1_1") (pintype "passive"))
    )
    (net (code "13") (name "/CON2_USB_P") (class "Default")
      (node (ref "D8") (pin "2") (pinfunction "2_2") (pintype "passive"))
      (node (ref "J4") (pin "A6") (pinfunction "DP1_A6") (pintype "passive"))
      (node (ref "J4") (pin "B6") (pinfunction "DP2_B6") (pintype "passive"))
      (node (ref "R24") (pin "1") (pinfunction "1_1") (pintype "passive"))
    )
    (net (code "14") (name "/CON_ESP_USB_N") (class "Default")
      (node (ref "J2") (pin "21") (pinfunction "21_21") (pintype "passive"))
      (node (ref "R25") (pin "1") (pinfunction "1_1") (pintype "passive"))
    )
    (net (code "15") (name "/CON_ESP_USB_P") (class "Default")
      (node (ref "J2") (pin "20") (pinfunction "20_20") (pintype "passive"))
      (node (ref "R26") (pin "1") (pinfunction "1_1") (pintype "passive"))
    )
    (net (code "16") (name "/CON_GPIO0") (class "Default")
      (node (ref "J1") (pin "3") (pinfunction "3_3") (pintype "passive"))
      (node (ref "R21") (pin "1") (pinfunction "1_1") (pintype "passive"))
    )
    (net (code "17") (name "/DTR_FTDI") (class "Default")
      (node (ref "Q2") (pin "2") (pinfunction "E_2") (pintype "passive"))
      (node (ref "R16") (pin "1") (pinfunction "1_1") (pintype "passive"))
      (node (ref "U2") (pin "18") (pinfunction "~{DTR}_18") (pintype "passive"))
    )
    (net (code "18") (name "/ESP_USB_N") (class "Default")
      (node (ref "R23") (pin "2") (pinfunction "2_2") (pintype "passive"))
      (node (ref "R25") (pin "2") (pinfunction "2_2") (pintype "passive"))
      (node (ref "U1") (pin "23") (pinfunction "USB_D-/RTC_GPIO19/GPIO19/U1RTS/ADC2_CH8/CLK_OUT2_23") (pintype "passive"))
    )
    (net (code "19") (name "/ESP_USB_P") (class "Default")
      (node (ref "R24") (pin "2") (pinfunction "2_2") (pintype "passive"))
      (node (ref "R26") (pin "2") (pinfunction "2_2") (pintype "passive"))
      (node (ref "U1") (pin "24") (pinfunction "USB_D+/RTC_GPIO20/GPIO20/U1CTS/ADC2_CH9/CLK_OUT1_24") (pintype "passive"))
    )
    (net (code "20") (name "/FTDI_RESET") (class "Default")
      (node (ref "C7") (pin "2") (pinfunction "2_2") (pintype "passive"))
      (node (ref "R8") (pin "2") (pinfunction "2_2") (pintype "passive"))
      (node (ref "U2") (pin "11") (pinfunction "~{RESET}_11") (pintype "passive"))
    )
    (net (code "21") (name "/FTDI_USB_N") (class "Default")
      (node (ref "R6") (pin "2") (pinfunction "2_2") (pintype "passive"))
      (node (ref "U2") (pin "9") (pinfunction "USBDM_9") (pintype "passive"))
    )
    (net (code "22") (name "/FTDI_USB_P") (class "Default")
      (node (ref "R7") (pin "2") (pinfunction "2_2") (pintype "passive"))
      (node (ref "U2") (pin "8") (pinfunction "USBDP_8") (pintype "passive"))
    )
    (net (code "23") (name "/GPIO0") (class "Default")
      (node (ref "R21") (pin "2") (pinfunction "2_2") (pintype "passive"))
      (node (ref "R22") (pin "2") (pinfunction "2_2") (pintype "passive"))
      (node (ref "U1") (pin "4") (pinfunction "GPIO0/RTC_GPIO0_4") (pintype "passive"))
    )
    (net (code "24") (name "/GPIO1") (class "Default")
      (node (ref "J1") (pin "4") (pinfunction "4_4") (pintype "passive"))
      (node (ref "U1") (pin "5") (pinfunction "GPIO1/RTC_GPIO1/TOUCH1/ADC1_CH0_5") (pintype "passive"))
    )
    (net (code "25") (name "/GPIO2") (class "Default")
      (node (ref "D2") (pin "1") (pinfunction "1_1") (pintype "passive"))
      (node (ref "J1") (pin "5") (pinfunction "5_5") (pintype "passive"))
      (node (ref "U1") (pin "6") (pinfunction "GPIO2/RTC_GPIO2/TOUCH2/ADC1_CH1_6") (pintype "passive"))
    )
    (net (code "26") (name "/GPIO3") (class "Default")
      (node (ref "J1") (pin "6") (pinfunction "6_6") (pintype "passive"))
      (node (ref "U1") (pin "7") (pinfunction "GPIO3/RTC_GPIO3/TOUCH3/ADC1_CH2_7") (pintype "passive"))
    )
    (net (code "27") (name "/GPIO4") (class "Default")
      (node (ref "J1") (pin "7") (pinfunction "7_7") (pintype "passive"))
      (node (ref "U1") (pin "8") (pinfunction "GPIO4/RTC_GPIO4/TOUCH4/ADC1_CH3_8") (pintype "passive"))
    )
    (net (code "28") (name "/GPIO5") (class "Default")
      (node (ref "J1") (pin "8") (pinfunction "8_8") (pintype "passive"))
      (node (ref "U1") (pin "9") (pinfunction "GPIO5/RTC_GPIO5/TOUCH5/ADC1_CH4_9") (pintype "passive"))
    )
    (net (code "29") (name "/GPIO6") (class "Default")
      (node (ref "J1") (pin "9") (pinfunction "9_9") (pintype "passive"))
      (node (ref "U1") (pin "10") (pinfunction "GPIO6/RTC_GPIO6/TOUCH6/ADC1_CH5_10") (pintype "passive"))
    )
    (net (code "30") (name "/GPIO7") (class "Default")
      (node (ref "J1") (pin "10") (pinfunction "10_10") (pintype "passive"))
      (node (ref "U1") (pin "11") (pinfunction "GPIO7/RTC_GPIO7/TOUCH7/ADC1_CH6_11") (pintype "passive"))
    )
    (net (code "31") (name "/GPIO8") (class "Default")
      (node (ref "J1") (pin "11") (pinfunction "11_11") (pintype "passive"))
      (node (ref "U1") (pin "12") (pinfunction "GPIO8/RTC_GPIO8/TOUCH8/ADC1_CH7/SUBSPICS1_12") (pintype "passive"))
    )
    (net (code "32") (name "/GPIO9") (class "Default")
      (node (ref "J1") (pin "12") (pinfunction "12_12") (pintype "passive"))
      (node (ref "U1") (pin "13") (pinfunction "GPIO9/RTC_GPIO9/TOUCH9/ADC1_CH8/FSPIHD/SUBSPIHD_13") (pintype "passive"))
    )
    (net (code "33") (name "/GPIO10") (class "Default")
      (node (ref "J1") (pin "13") (pinfunction "13_13") (pintype "passive"))
      (node (ref "U1") (pin "14") (pinfunction "GPIO10/RTC_GPIO10/TOUCH10/ADC1_CH9/FSPICS0/FSPIIO4/SUBSPICS0_14") (pintype "passive"))
    )
    (net (code "34") (name "/GPIO11") (class "Default")
      (node (ref "J1") (pin "14") (pinfunction "14_14") (pintype "passive"))
      (node (ref "U1") (pin "15") (pinfunction "GPIO11/RTC_GPIO11/TOUCH11/ADC2_CH0/FSPID/FSPIIO5/SUBSPID_15") (pintype "passive"))
    )
    (net (code "35") (name "/GPIO12") (class "Default")
      (node (ref "J1") (pin "15") (pinfunction "15_15") (pintype "passive"))
      (node (ref "U1") (pin "16") (pinfunction "GPIO12/RTC_GPIO12/TOUCH12/ADC2_CH1/FSPICLK/FSPIIO6/SUBSPICLK_16") (pintype "passive"))
    )
    (net (code "36") (name "/GPIO13") (class "Default")
      (node (ref "J1") (pin "16") (pinfunction "16_16") (pintype "passive"))
      (node (ref "U1") (pin "17") (pinfunction "GPIO13/RTC_GPIO13/TOUCH13/ADC2_CH2/FSPIQ/FSPIIO7/SUBSPIQ_17") (pintype "passive"))
    )
    (net (code "37") (name "/GPIO14") (class "Default")
      (node (ref "J1") (pin "17") (pinfunction "17_17") (pintype "passive"))
      (node (ref "U1") (pin "18") (pinfunction "GPIO14/RTC_GPIO14/TOUCH14/ADC2_CH3/FSPIWP/FSPIDQS/SUBSPIWP_18") (pintype "passive"))
    )
    (net (code "38") (name "/GPIO15") (class "Default")
      (node (ref "J1") (pin "18") (pinfunction "18_18") (pintype "passive"))
      (node (ref "U1") (pin "19") (pinfunction "GPIO15/RTC_GPIO15/U0RTS/ADC2_CH4/XTAL_32K_P_19") (pintype "passive"))
    )
    (net (code "39") (name "/GPIO16") (class "Default")
      (node (ref "J1") (pin "19") (pinfunction "19_19") (pintype "passive"))
      (node (ref "U1") (pin "20") (pinfunction "GPIO16/RTC_GPIO16/U0CTS/ADC2_CH5/XTAL_32K_N_20") (pintype "passive"))
    )
    (net (code "40") (name "/GPIO17") (class "Default")
      (node (ref "J1") (pin "20") (pinfunction "20_20") (pintype "passive"))
      (node (ref "U1") (pin "21") (pinfunction "GPIO17/RTC_GPIO17/U1TXD/ADC2_CH6_21") (pintype "passive"))
    )
    (net (code "41") (name "/GPIO18") (class "Default")
      (node (ref "J1") (pin "21") (pinfunction "21_21") (pintype "passive"))
      (node (ref "U1") (pin "22") (pinfunction "GPIO18/RTC_GPIO18/U1RXD/ADC2_CH7/CLK_OUT3_22") (pintype "passive"))
    )
    (net (code "42") (name "/GPIO21") (class "Default")
      (node (ref "J2") (pin "19") (pinfunction "19_19") (pintype "passive"))
      (node (ref "U1") (pin "25") (pinfunction "GPIO21/RTC_GPIO21_25") (pintype "passive"))
    )
    (net (code "43") (name "/GPIO26") (class "Default")
      (node (ref "J2") (pin "18") (pinfunction "18_18") (pintype "passive"))
      (node (ref "U1") (pin "26") (pinfunction "GPIO26/SPICS1_26") (pintype "passive"))
    )
    (net (code "44") (name "/GPIO33") (class "Default")
      (node (ref "J2") (pin "17") (pinfunction "17_17") (pintype "passive"))
      (node (ref "U1") (pin "28") (pinfunction "GPIO33/SPIIO4/FSPIHD/SUBSPIHD_28") (pintype "passive"))
    )
    (net (code "45") (name "/GPIO34") (class "Default")
      (node (ref "J2") (pin "16") (pinfunction "16_16") (pintype "passive"))
      (node (ref "U1") (pin "29") (pinfunction "GPIO34/SPIIO5/FSPICS0/SUBSPICS0_29") (pintype "passive"))
    )
    (net (code "46") (name "/GPIO35") (class "Default")
      (node (ref "J2") (pin "15") (pinfunction "15_15") (pintype "passive"))
      (node (ref "U1") (pin "31") (pinfunction "GPIO35/SPIIO6/FSPID/SUBSPID_31") (pintype "passive"))
    )
    (net (code "47") (name "/GPIO36") (class "Default")
      (node (ref "J2") (pin "14") (pinfunction "14_14") (pintype "passive"))
      (node (ref "U1") (pin "32") (pinfunction "GPIO36/SPIIO7/FSPICLK/SUBSPICLK_32") (pintype "passive"))
    )
    (net (code "48") (name "/GPIO37") (class "Default")
      (node (ref "J2") (pin "13") (pinfunction "13_13") (pintype "passive"))
      (node (ref "U1") (pin "33") (pinfunction "GPIO37/SPIDQS/FSPIQ/SUBSPIQ_33") (pintype "passive"))
    )
    (net (code "49") (name "/GPIO38") (class "Default")
      (node (ref "J2") (pin "12") (pinfunction "12_12") (pintype "passive"))
      (node (ref "U1") (pin "34") (pinfunction "GPIO38/FSPIWP/SUBSPIWP_34") (pintype "passive"))
    )
    (net (code "50") (name "/GPIO39") (class "Default")
      (node (ref "J2") (pin "11") (pinfunction "11_11") (pintype "passive"))
      (node (ref "U1") (pin "35") (pinfunction "MTCK/GPIO39/CLK_OUT3/SUBSPICS1_35") (pintype "passive"))
    )
    (net (code "51") (name "/GPIO40") (class "Default")
      (node (ref "J2") (pin "10") (pinfunction "10_10") (pintype "passive"))
      (node (ref "U1") (pin "36") (pinfunction "MTDO/GPIO40/CLK_OUT2_36") (pintype "passive"))
    )
    (net (code "52") (name "/GPIO41") (class "Default")
      (node (ref "J2") (pin "9") (pinfunction "9_9") (pintype "passive"))
      (node (ref "U1") (pin "37") (pinfunction "MTDI/GPIO41/CLK_OUT1_37") (pintype "passive"))
    )
    (net (code "53") (name "/GPIO42") (class "Default")
      (node (ref "J2") (pin "8") (pinfunction "8_8") (pintype "passive"))
      (node (ref "U1") (pin "38") (pinfunction "MTMS/GPIO42_38") (pintype "passive"))
    )
    (net (code "54") (name "/GPIO45") (class "Default")
      (node (ref "J2") (pin "5") (pinfunction "5_5") (pintype "passive"))
      (node (ref "U1") (pin "41") (pinfunction "GPIO45_41") (pintype "passive"))
    )
    (net (code "55") (name "/GPIO46") (class "Default")
      (node (ref "J2") (pin "4") (pinfunction "4_4") (pintype "passive"))
      (node (ref "U1") (pin "44") (pinfunction "GPIO46_44") (pintype "passive"))
    )
    (net (code "56") (name "/GPIO47") (class "Default")
      (node (ref "J2") (pin "23") (pinfunction "23_23") (pintype "passive"))
      (node (ref "U1") (pin "27") (pinfunction "GPIO47/SPICLK_P_DIFF/SUBSPICLK_P_DIFF_27") (pintype "passive"))
    )
    (net (code "57") (name "/GPIO48") (class "Default")
      (node (ref "J2") (pin "22") (pinfunction "22_22") (pintype "passive"))
      (node (ref "U1") (pin "30") (pinfunction "GPIO48/SPICLK_N_DIFF/SUBSPICLK_N_DIFF_30") (pintype "passive"))
    )
    (net (code "58") (name "/RTS_FTDI") (class "Default")
      (node (ref "Q1") (pin "2") (pinfunction "E_2") (pintype "passive"))
      (node (ref "R18") (pin "1") (pinfunction "1_1") (pintype "passive"))
      (node (ref "U2") (pin "19") (pinfunction "~{RTS}_19") (pintype "passive"))
    )
    (net (code "59") (name "/RXD_FTDI") (class "Default")
      (node (ref "R19") (pin "2") (pinfunction "2_2") (pintype "passive"))
      (node (ref "U2") (pin "1") (pinfunction "RXD_1") (pintype "passive"))
    )
    (net (code "60") (name "/TXD_FTDI") (class "Default")
      (node (ref "R20") (pin "2") (pinfunction "2_2") (pintype "passive"))
      (node (ref "U2") (pin "17") (pinfunction "TXD_17") (pintype "passive"))
    )
    (net (code "61") (name "/U0RXD") (class "Default")
      (node (ref "J2") (pin "6") (pinfunction "6_6") (pintype "passive"))
      (node (ref "R20") (pin "1") (pinfunction "1_1") (pintype "passive"))
      (node (ref "U1") (pin "40") (pinfunction "U0RXD/GPIO44/CLK_OUT2_40") (pintype "passive"))
    )
    (net (code "62") (name "/U0TXD") (class "Default")
      (node (ref "J2") (pin "7") (pinfunction "7_7") (pintype "passive"))
      (node (ref "R19") (pin "1") (pinfunction "1_1") (pintype "passive"))
      (node (ref "U1") (pin "39") (pinfunction "U0TXD/GPIO43/CLK_OUT1_39") (pintype "passive"))
    )
    (net (code "63") (name "/VBUS_SENSE") (class "Default")
      (node (ref "R10") (pin "1") (pinfunction "1_1") (pintype "passive"))
      (node (ref "R13") (pin "1") (pinfunction "1_1") (pintype "passive"))
      (node (ref "U2") (pin "16") (pinfunction "CBUS3_16") (pintype "passive"))
    )
    (net (code "64") (name "GND") (class "Default")
      (node (ref "C1") (pin "1") (pinfunction "1_1") (pintype "passive"))
      (node (ref "C10") (pin "1") (pinfunction "1_1") (pintype "passive"))
      (node (ref "C11") (pin "1") (pinfunction "1_1") (pintype "passive"))
      (node (ref "C12") (pin "1") (pinfunction "1_1") (pintype "passive"))
      (node (ref "C13") (pin "1") (pinfunction "1_1") (pintype "passive"))
      (node (ref "C14") (pin "1") (pinfunction "1_1") (pintype "passive"))
      (node (ref "C15") (pin "1") (pinfunction "1_1") (pintype "passive"))
      (node (ref "C16") (pin "1") (pinfunction "1_1") (pintype "passive"))
      (node (ref "C17") (pin "1") (pinfunction "1_1") (pintype "passive"))
      (node (ref "C2") (pin "1") (pinfunction "1_1") (pintype "passive"))
      (node (ref "C3") (pin "1") (pinfunction "1_1") (pintype "passive"))
      (node (ref "C4") (pin "1") (pinfunction "1_1") (pintype "passive"))
      (node (ref "C5") (pin "1") (pinfunction "1_1") (pintype "passive"))
      (node (ref "C6") (pin "1") (pinfunction "1_1") (pintype "passive"))
      (node (ref "C7") (pin "1") (pinfunction "1_1") (pintype "passive"))
      (node (ref "C8") (pin "1") (pinfunction "1_1") (pintype "passive"))
      (node (ref "C9") (pin "1") (pinfunction "1_1") (pintype "passive"))
      (node (ref "D1") (pin "1") (pinfunction "1_1") (pintype "passive"))
      (node (ref "D3") (pin "1") (pinfunction "1_1") (pintype "passive"))
      (node (ref "D4") (pin "1") (pinfunction "1_1") (pintype "passive"))
      (node (ref "D5") (pin "1") (pinfunction "1_1") (pintype "passive"))
      (node (ref "D6") (pin "1") (pinfunction "1_1") (pintype "passive"))
      (node (ref "D7") (pin "1") (pinfunction "1_1") (pintype "passive"))
      (node (ref "D8") (pin "1") (pinfunction "1_1") (pintype "passive"))
      (node (ref "J1") (pin "1") (pinfunction "1_1") (pintype "passive"))
      (node (ref "J1") (pin "23") (pinfunction "23_23") (pintype "passive"))
      (node (ref "J2") (pin "2") (pinfunction "2_2") (pintype "passive"))
      (node (ref "J2") (pin "24") (pinfunction "24_24") (pintype "passive"))
      (node (ref "J3") (pin "A1B12") (pinfunction "GND_A1B12_A1B12") (pintype "passive"))
      (node (ref "J3") (pin "B1A12") (pinfunction "GND_B1A12_B1A12") (pintype "passive"))
      (node (ref "J3") (pin "S1") (pinfunction "SHIELD_1_S1") (pintype "passive"))
      (node (ref "J3") (pin "S2") (pinfunction "SHIELD_2_S2") (pintype "passive"))
      (node (ref "J3") (pin "S3") (pinfunction "SHIELD_3_S3") (pintype "passive"))
      (node (ref "J3") (pin "S4") (pinfunction "SHIELD_4_S4") (pintype "passive"))
      (node (ref "J4") (pin "A1B12") (pinfunction "GND_A1B12_A1B12") (pintype "passive"))
      (node (ref "J4") (pin "B1A12") (pinfunction "GND_B1A12_B1A12") (pintype "passive"))
      (node (ref "J4") (pin "S1") (pinfunction "SHIELD_1_S1") (pintype "passive"))
      (node (ref "J4") (pin "S2") (pinfunction "SHIELD_2_S2") (pintype "passive"))
      (node (ref "J4") (pin "S3") (pinfunction "SHIELD_3_S3") (pintype "passive"))
      (node (ref "J4") (pin "S4") (pinfunction "SHIELD_4_S4") (pintype "passive"))
      (node (ref "R11") (pin "1") (pinfunction "1_1") (pintype "passive"))
      (node (ref "R12") (pin "1") (pinfunction "1_1") (pintype "passive"))
      (node (ref "R13") (pin "2") (pinfunction "2_2") (pintype "passive"))
      (node (ref "R14") (pin "1") (pinfunction "1_1") (pintype "passive"))
      (node (ref "R15") (pin "1") (pinfunction "1_1") (pintype "passive"))
      (node (ref "R9") (pin "2") (pinfunction "2_2") (pintype "passive"))
      (node (ref "SW1") (pin "3") (pinfunction "3_3") (pintype "passive"))
      (node (ref "SW1") (pin "4") (pinfunction "4_4") (pintype "passive"))
      (node (ref "SW2") (pin "3") (pinfunction "3_3") (pintype "passive"))
      (node (ref "SW2") (pin "4") (pinfunction "4_4") (pintype "passive"))
      (node (ref "U1") (pin "1") (pinfunction "GND_01_1") (pintype "passive"))
      (node (ref "U1") (pin "2") (pinfunction "GND_02_2") (pintype "passive"))
      (node (ref "U1") (pin "42") (pinfunction "GND_42") (pintype "passive"))
      (node (ref "U1") (pin "43") (pinfunction "GND_43") (pintype "passive"))
      (node (ref "U1") (pin "46") (pinfunction "GND_46_46") (pintype "passive"))
      (node (ref "U1") (pin "47") (pinfunction "GND_47_47") (pintype "passive"))
      (node (ref "U1") (pin "48") (pinfunction "GND_48_48") (pintype "passive"))
      (node (ref "U1") (pin "49") (pinfunction "GND_49_49") (pintype "passive"))
      (node (ref "U1") (pin "50") (pinfunction "GND_50_50") (pintype "passive"))
      (node (ref "U1") (pin "51") (pinfunction "GND_51_51") (pintype "passive"))
      (node (ref "U1") (pin "52") (pinfunction "GND_52_52") (pintype "passive"))
      (node (ref "U1") (pin "53") (pinfunction "GND_53_53") (pintype "passive"))
      (node (ref "U1") (pin "54") (pinfunction "GND_54_54") (pintype "passive"))
      (node (ref "U1") (pin "55") (pinfunction "GND_55_55") (pintype "passive"))
      (node (ref "U1") (pin "56") (pinfunction "GND_56_56") (pintype "passive"))
      (node (ref "U1") (pin "57") (pinfunction "GND_57_57") (pintype "passive"))
      (node (ref "U1") (pin "58") (pinfunction "GND_58_58") (pintype "passive"))
      (node (ref "U1") (pin "59") (pinfunction "GND_59_59") (pintype "passive"))
      (node (ref "U1") (pin "60") (pinfunction "GND_60_60") (pintype "passive"))
      (node (ref "U1") (pin "61") (pinfunction "GND_61_61") (pintype "passive"))
      (node (ref "U1") (pin "62") (pinfunction "GND_62_62") (pintype "passive"))
      (node (ref "U1") (pin "63") (pinfunction "GND_63_63") (pintype "passive"))
      (node (ref "U1") (pin "64") (pinfunction "GND_64_64") (pintype "passive"))
      (node (ref "U1") (pin "65") (pinfunction "GND_65_65") (pintype "passive"))
      (node (ref "U1") (pin "66") (pinfunction "GND_66_66") (pintype "passive"))
      (node (ref "U1") (pin "67") (pinfunction "GND_67_67") (pintype "passive"))
      (node (ref "U1") (pin "68") (pinfunction "GND_68_68") (pintype "passive"))
      (node (ref "U1") (pin "69") (pinfunction "GND_69_69") (pintype "passive"))
      (node (ref "U1") (pin "70") (pinfunction "GND_70_70") (pintype "passive"))
      (node (ref "U1") (pin "71") (pinfunction "GND_71_71") (pintype "passive"))
      (node (ref "U1") (pin "72") (pinfunction "GND_72_72") (pintype "passive"))
      (node (ref "U1") (pin "73") (pinfunction "GND_73_73") (pintype "passive"))
      (node (ref "U2") (pin "13") (pinfunction "GND_13") (pintype "passive"))
      (node (ref "U2") (pin "21") (pinfunction "GND_21") (pintype "passive"))
      (node (ref "U2") (pin "3") (pinfunction "GND_3") (pintype "passive"))
      (node (ref "U3") (pin "2") (pinfunction "GND_2") (pintype "power_in"))
      (node (ref "U3") (pin "4") (pinfunction "GND_4") (pintype "power_in"))
    )
    (net (code "65") (name "Net-(D1-Pad2)") (class "Default")
      (node (ref "D1") (pin "2") (pinfunction "2_2") (pintype "passive"))
      (node (ref "R3") (pin "1") (pinfunction "1_1") (pintype "passive"))
    )
    (net (code "66") (name "Net-(D2-Pad2)") (class "Default")
      (node (ref "D2") (pin "2") (pinfunction "2_2") (pintype "passive"))
      (node (ref "R4") (pin "1") (pinfunction "1_1") (pintype "passive"))
    )
    (net (code "67") (name "Net-(J3-CC1)") (class "Default")
      (node (ref "J3") (pin "A5") (pinfunction "CC1_A5") (pintype "passive"))
      (node (ref "R12") (pin "2") (pinfunction "2_2") (pintype "passive"))
    )
    (net (code "68") (name "Net-(J3-CC2)") (class "Default")
      (node (ref "J3") (pin "B5") (pinfunction "CC2_B5") (pintype "passive"))
      (node (ref "R11") (pin "2") (pinfunction "2_2") (pintype "passive"))
    )
    (net (code "69") (name "Net-(J4-CC1)") (class "Default")
      (node (ref "J4") (pin "A5") (pinfunction "CC1_A5") (pintype "passive"))
      (node (ref "R15") (pin "2") (pinfunction "2_2") (pintype "passive"))
    )
    (net (code "70") (name "Net-(J4-CC2)") (class "Default")
      (node (ref "J4") (pin "B5") (pinfunction "CC2_B5") (pintype "passive"))
      (node (ref "R14") (pin "2") (pinfunction "2_2") (pintype "passive"))
    )
    (net (code "71") (name "Net-(Q1-B)") (class "Default")
      (node (ref "Q1") (pin "1") (pinfunction "B_1") (pintype "passive"))
      (node (ref "R16") (pin "2") (pinfunction "2_2") (pintype "passive"))
    )
    (net (code "72") (name "Net-(Q2-B)") (class "Default")
      (node (ref "Q2") (pin "1") (pinfunction "B_1") (pintype "passive"))
      (node (ref "R18") (pin "2") (pinfunction "2_2") (pintype "passive"))
    )
    (net (code "73") (name "Net-(U2-CBUS0)") (class "Default")
      (node (ref "R9") (pin "1") (pinfunction "1_1") (pintype "passive"))
      (node (ref "U2") (pin "15") (pinfunction "CBUS0_15") (pintype "passive"))
    )
    (net (code "74") (name "unconnected-(J1-Pad24)") (class "Default")
      (node (ref "J1") (pin "24") (pinfunction "24_24") (pintype "passive+no_connect"))
    )
    (net (code "75") (name "unconnected-(J3-SBU1-PadA8)") (class "Default")
      (node (ref "J3") (pin "A8") (pinfunction "SBU1_A8") (pintype "passive+no_connect"))
    )
    (net (code "76") (name "unconnected-(J3-SBU2-PadB8)") (class "Default")
      (node (ref "J3") (pin "B8") (pinfunction "SBU2_B8") (pintype "passive+no_connect"))
    )
    (net (code "77") (name "unconnected-(J4-SBU1-PadA8)") (class "Default")
      (node (ref "J4") (pin "A8") (pinfunction "SBU1_A8") (pintype "passive+no_connect"))
    )
    (net (code "78") (name "unconnected-(J4-SBU2-PadB8)") (class "Default")
      (node (ref "J4") (pin "B8") (pinfunction "SBU2_B8") (pintype "passive+no_connect"))
    )
    (net (code "79") (name "unconnected-(U2-CBUS1-Pad14)") (class "Default")
      (node (ref "U2") (pin "14") (pinfunction "CBUS1_14") (pintype "passive+no_connect"))
    )
    (net (code "80") (name "unconnected-(U2-CBUS2-Pad7)") (class "Default")
      (node (ref "U2") (pin "7") (pinfunction "CBUS2_7") (pintype "passive+no_connect"))
    )
    (net (code "81") (name "unconnected-(U2-~{CTS}-Pad6)") (class "Default")
      (node (ref "U2") (pin "6") (pinfunction "~{CTS}_6") (pintype "passive+no_connect"))
    )
    (net (code "82") (name "unconnected-(U2-~{DCD}-Pad5)") (class "Default")
      (node (ref "U2") (pin "5") (pinfunction "~{DCD}_5") (pintype "passive+no_connect"))
    )
    (net (code "83") (name "unconnected-(U2-~{DSR}-Pad4)") (class "Default")
      (node (ref "U2") (pin "4") (pinfunction "~{DSR}_4") (pintype "passive+no_connect"))
    )
    (net (code "84") (name "unconnected-(U2-~{RI}-Pad2)") (class "Default")
      (node (ref "U2") (pin "2") (pinfunction "~{RI}_2") (pintype "passive+no_connect"))
    )
  )
)
